# connector-test.net
KiCad netlist of a schematic drawn in EAGLE
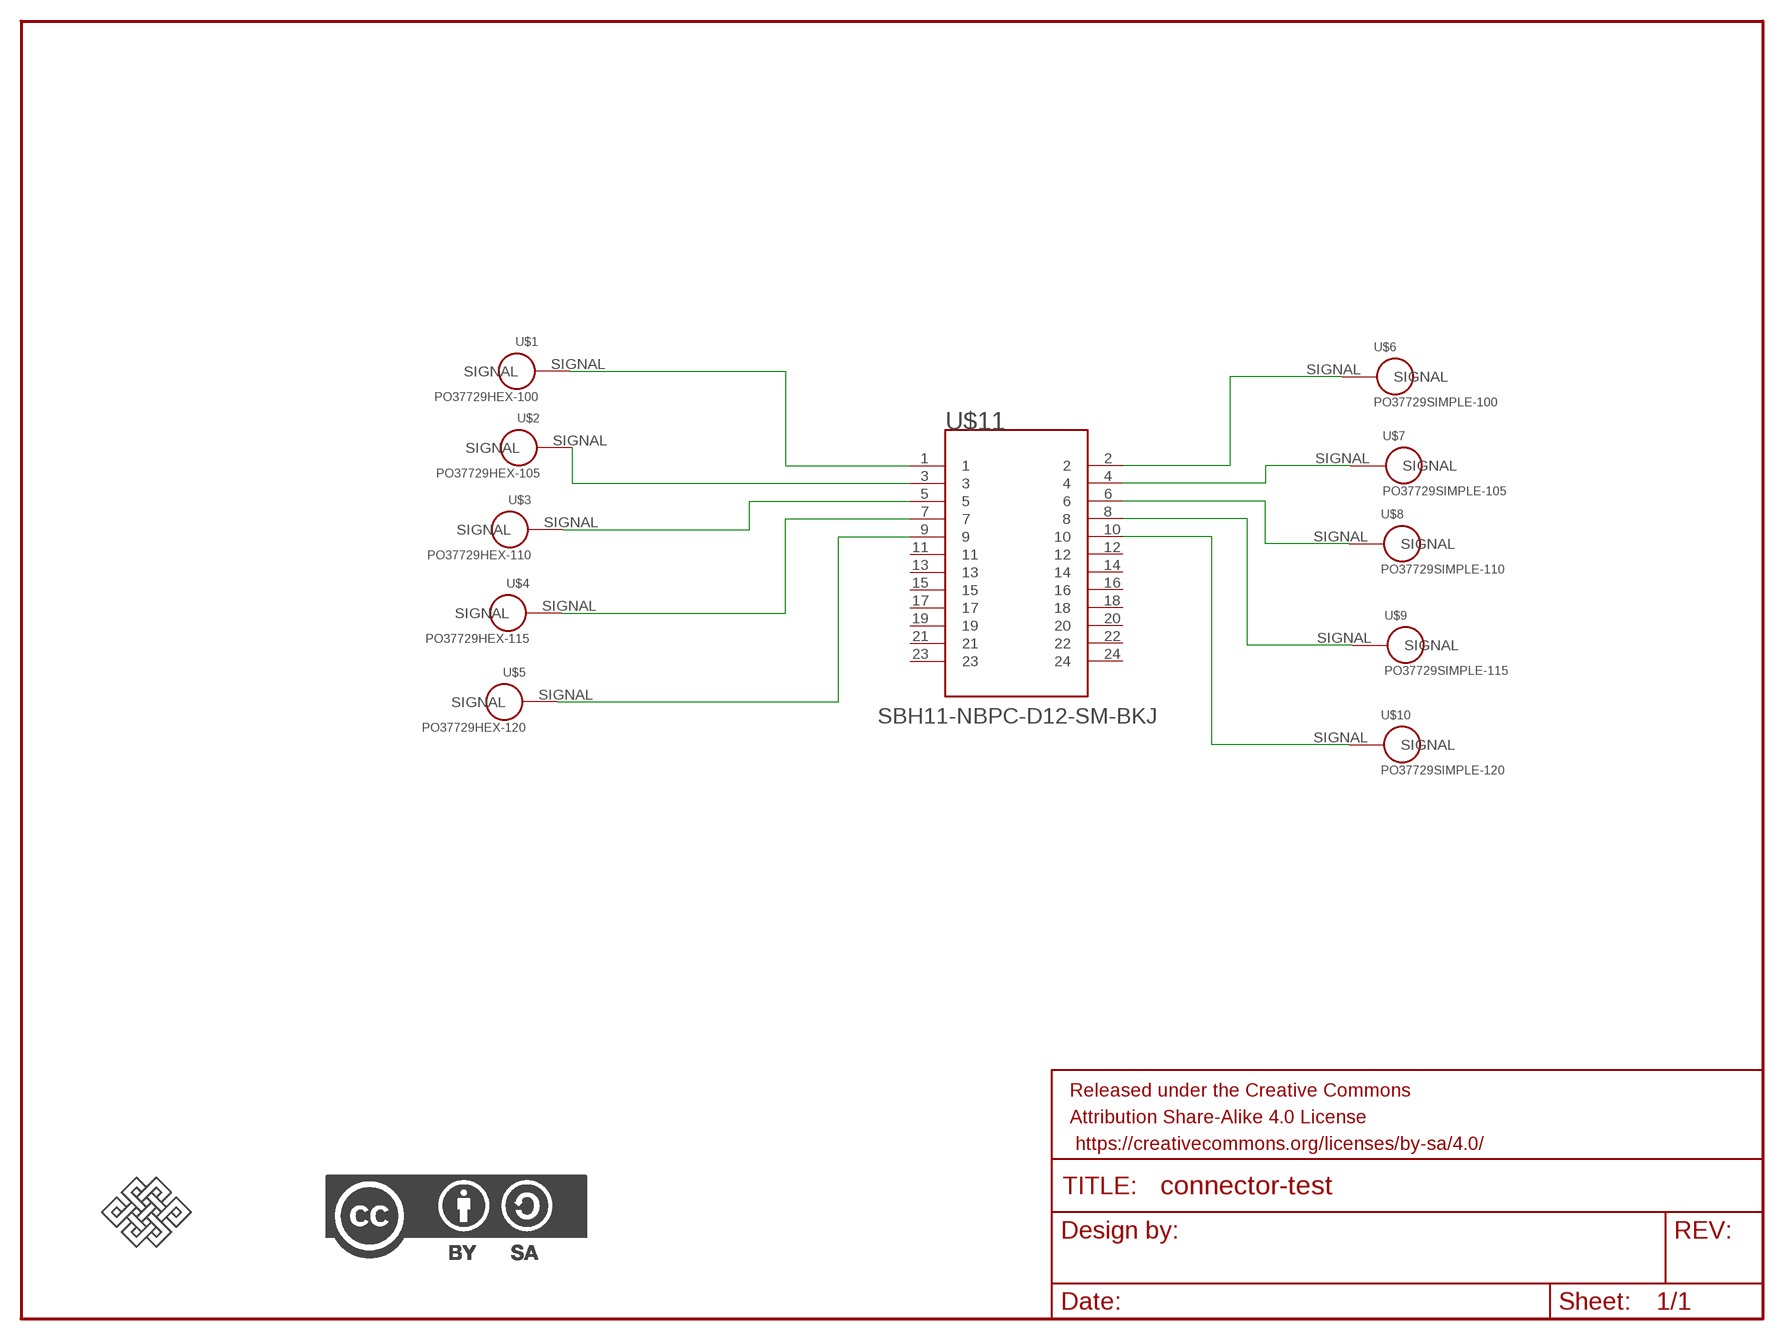
[diagram p0: schematic, sheet 1]

(export (version "E")
  (design (tool "Eeschema 10.0.6"))
  (components
    (comp (ref "FRAME1")
      (value "FRAME-LETTER")
      (footprint "eagle-import:CREATIVE_COMMONS")
      (libsource (lib "eagle-import") (part "FRAME-LETTER"))
    )
    (comp (ref "U$1")
      (value "PO37729HEX-100")
      (footprint "eagle-import:HEX-100")
      (libsource (lib "eagle-import") (part "PO37729HEX-100"))
    )
    (comp (ref "U$2")
      (value "PO37729HEX-105")
      (footprint "eagle-import:HEX-105")
      (libsource (lib "eagle-import") (part "PO37729HEX-105"))
    )
    (comp (ref "U$3")
      (value "PO37729HEX-110")
      (footprint "eagle-import:HEX-110")
      (libsource (lib "eagle-import") (part "PO37729HEX-110"))
    )
    (comp (ref "U$4")
      (value "PO37729HEX-115")
      (footprint "eagle-import:HEX-115")
      (libsource (lib "eagle-import") (part "PO37729HEX-115"))
    )
    (comp (ref "U$5")
      (value "PO37729HEX-120")
      (footprint "eagle-import:HEX-120")
      (libsource (lib "eagle-import") (part "PO37729HEX-120"))
    )
    (comp (ref "U$6")
      (value "PO37729SIMPLE-100")
      (footprint "eagle-import:SIMPLE-100")
      (libsource (lib "eagle-import") (part "PO37729SIMPLE-100"))
    )
    (comp (ref "U$7")
      (value "PO37729SIMPLE-105")
      (footprint "eagle-import:SIMPLE-105")
      (libsource (lib "eagle-import") (part "PO37729SIMPLE-105"))
    )
    (comp (ref "U$8")
      (value "PO37729SIMPLE-110")
      (footprint "eagle-import:SIMPLE-110")
      (libsource (lib "eagle-import") (part "PO37729SIMPLE-110"))
    )
    (comp (ref "U$9")
      (value "PO37729SIMPLE-115")
      (footprint "eagle-import:SIMPLE-115")
      (libsource (lib "eagle-import") (part "PO37729SIMPLE-115"))
    )
    (comp (ref "U$10")
      (value "PO37729SIMPLE-120")
      (footprint "eagle-import:SIMPLE-120")
      (libsource (lib "eagle-import") (part "PO37729SIMPLE-120"))
    )
    (comp (ref "U$11")
      (value "SBH11-NBPC-D12-SM-BKJ")
      (footprint "eagle-import:SBH11-NBPC-D12-SM-BK")
      (fields
        (field (name "MF") "SULLINS")
        (field (name "MP") "SBH11-NBPC-D12-SM-BK")
        (field (name "AUTHOR") "Adam Feuer")
      )
      (libsource (lib "eagle-import") (part "SBH11-NBPC-D12-SM-BKJ"))
    )
    (comp (ref "U$12")
      (value "ENDLESSKNOTENDLESSKNOT-LARGE")
      (footprint "eagle-import:ENDLESSKNOT")
      (libsource (lib "eagle-import") (part "ENDLESSKNOTENDLESSKNOT-LARGE"))
    )
    (comp (ref "U$13")
      (value "CC-BY-SA")
      (footprint "eagle-import:CC-BY-SA")
      (libsource (lib "eagle-import") (part "CC-BY-SA"))
    )
  )
  (nets
    (net (code "1") (name "Net-(U$1-PadSIGNAL)") (class "Default")
      (node (ref "U$1") (pin "SIGNAL") (pinfunction "SIGNAL_SIGNAL") (pintype "bidirectional"))
      (node (ref "U$11") (pin "1") (pinfunction "1_1") (pintype "passive"))
    )
    (net (code "2") (name "Net-(U$10-PadSIGNAL)") (class "Default")
      (node (ref "U$10") (pin "SIGNAL") (pinfunction "SIGNAL_SIGNAL") (pintype "bidirectional"))
      (node (ref "U$11") (pin "10") (pinfunction "10_10") (pintype "passive"))
    )
    (net (code "3") (name "Net-(U$11-Pad2)") (class "Default")
      (node (ref "U$11") (pin "2") (pinfunction "2_2") (pintype "passive"))
      (node (ref "U$6") (pin "SIGNAL") (pinfunction "SIGNAL_SIGNAL") (pintype "bidirectional"))
    )
    (net (code "4") (name "Net-(U$11-Pad3)") (class "Default")
      (node (ref "U$11") (pin "3") (pinfunction "3_3") (pintype "passive"))
      (node (ref "U$2") (pin "SIGNAL") (pinfunction "SIGNAL_SIGNAL") (pintype "bidirectional"))
    )
    (net (code "5") (name "Net-(U$11-Pad4)") (class "Default")
      (node (ref "U$11") (pin "4") (pinfunction "4_4") (pintype "passive"))
      (node (ref "U$7") (pin "SIGNAL") (pinfunction "SIGNAL_SIGNAL") (pintype "bidirectional"))
    )
    (net (code "6") (name "Net-(U$11-Pad5)") (class "Default")
      (node (ref "U$11") (pin "5") (pinfunction "5_5") (pintype "passive"))
      (node (ref "U$3") (pin "SIGNAL") (pinfunction "SIGNAL_SIGNAL") (pintype "bidirectional"))
    )
    (net (code "7") (name "Net-(U$11-Pad6)") (class "Default")
      (node (ref "U$11") (pin "6") (pinfunction "6_6") (pintype "passive"))
      (node (ref "U$8") (pin "SIGNAL") (pinfunction "SIGNAL_SIGNAL") (pintype "bidirectional"))
    )
    (net (code "8") (name "Net-(U$11-Pad7)") (class "Default")
      (node (ref "U$11") (pin "7") (pinfunction "7_7") (pintype "passive"))
      (node (ref "U$4") (pin "SIGNAL") (pinfunction "SIGNAL_SIGNAL") (pintype "bidirectional"))
    )
    (net (code "9") (name "Net-(U$11-Pad8)") (class "Default")
      (node (ref "U$11") (pin "8") (pinfunction "8_8") (pintype "passive"))
      (node (ref "U$9") (pin "SIGNAL") (pinfunction "SIGNAL_SIGNAL") (pintype "bidirectional"))
    )
    (net (code "10") (name "Net-(U$11-Pad9)") (class "Default")
      (node (ref "U$11") (pin "9") (pinfunction "9_9") (pintype "passive"))
      (node (ref "U$5") (pin "SIGNAL") (pinfunction "SIGNAL_SIGNAL") (pintype "bidirectional"))
    )
    (net (code "11") (name "unconnected-(U$11-Pad11)") (class "Default")
      (node (ref "U$11") (pin "11") (pinfunction "11_11") (pintype "passive"))
    )
    (net (code "12") (name "unconnected-(U$11-Pad12)") (class "Default")
      (node (ref "U$11") (pin "12") (pinfunction "12_12") (pintype "passive"))
    )
    (net (code "13") (name "unconnected-(U$11-Pad13)") (class "Default")
      (node (ref "U$11") (pin "13") (pinfunction "13_13") (pintype "passive"))
    )
    (net (code "14") (name "unconnected-(U$11-Pad14)") (class "Default")
      (node (ref "U$11") (pin "14") (pinfunction "14_14") (pintype "passive"))
    )
    (net (code "15") (name "unconnected-(U$11-Pad15)") (class "Default")
      (node (ref "U$11") (pin "15") (pinfunction "15_15") (pintype "passive"))
    )
    (net (code "16") (name "unconnected-(U$11-Pad16)") (class "Default")
      (node (ref "U$11") (pin "16") (pinfunction "16_16") (pintype "passive"))
    )
    (net (code "17") (name "unconnected-(U$11-Pad17)") (class "Default")
      (node (ref "U$11") (pin "17") (pinfunction "17_17") (pintype "passive"))
    )
    (net (code "18") (name "unconnected-(U$11-Pad18)") (class "Default")
      (node (ref "U$11") (pin "18") (pinfunction "18_18") (pintype "passive"))
    )
    (net (code "19") (name "unconnected-(U$11-Pad19)") (class "Default")
      (node (ref "U$11") (pin "19") (pinfunction "19_19") (pintype "passive"))
    )
    (net (code "20") (name "unconnected-(U$11-Pad20)") (class "Default")
      (node (ref "U$11") (pin "20") (pinfunction "20_20") (pintype "passive"))
    )
    (net (code "21") (name "unconnected-(U$11-Pad21)") (class "Default")
      (node (ref "U$11") (pin "21") (pinfunction "21_21") (pintype "passive"))
    )
    (net (code "22") (name "unconnected-(U$11-Pad22)") (class "Default")
      (node (ref "U$11") (pin "22") (pinfunction "22_22") (pintype "passive"))
    )
    (net (code "23") (name "unconnected-(U$11-Pad23)") (class "Default")
      (node (ref "U$11") (pin "23") (pinfunction "23_23") (pintype "passive"))
    )
    (net (code "24") (name "unconnected-(U$11-Pad24)") (class "Default")
      (node (ref "U$11") (pin "24") (pinfunction "24_24") (pintype "passive"))
    )
  )
)
